# shema.net
KiCad netlist of a schematic drawn in EAGLE
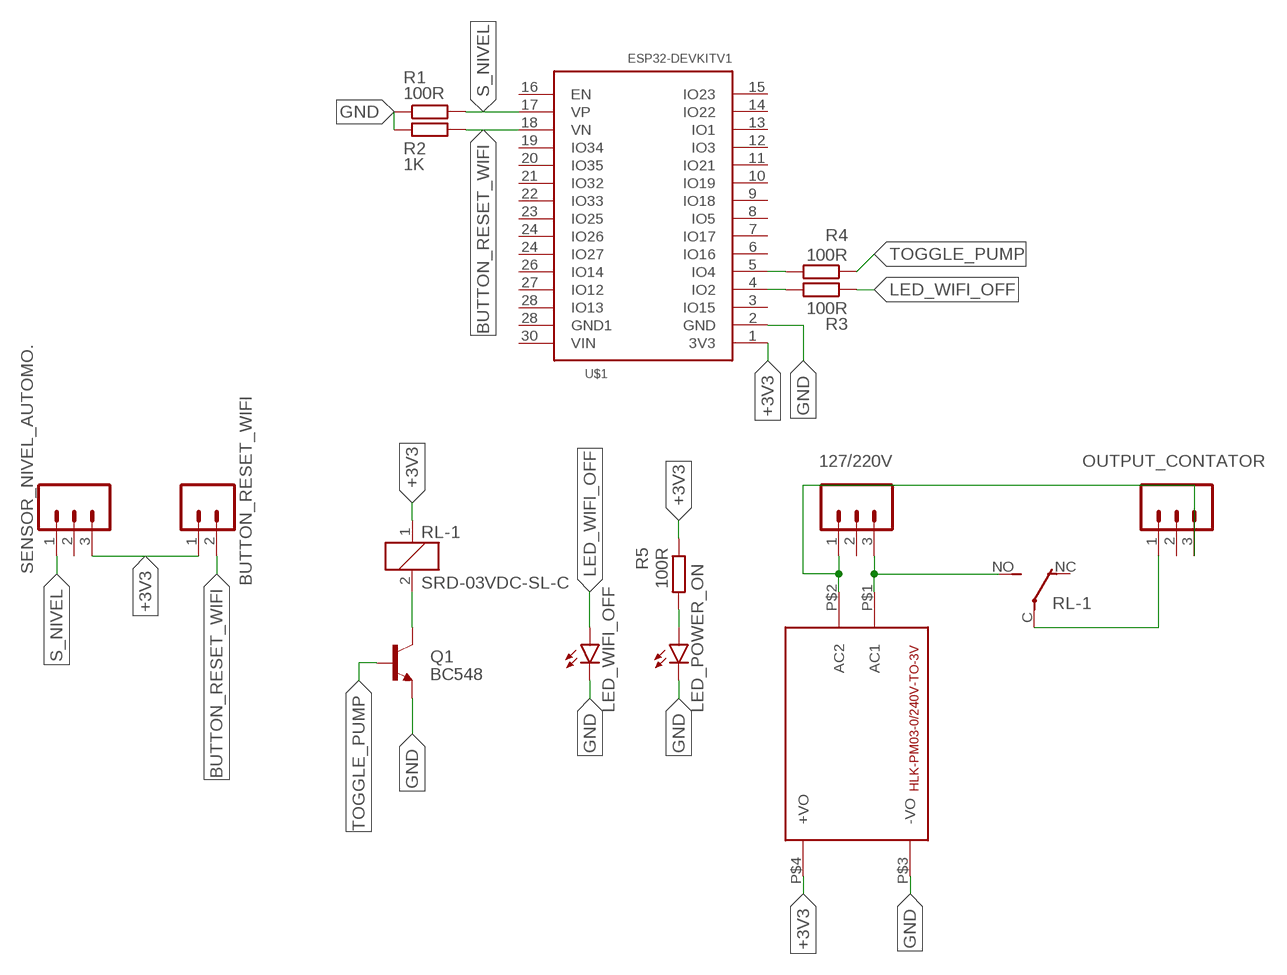
[diagram p0: schematic, sheet 1]

(export (version "E")
  (design (tool "Eeschema 10.0.6"))
  (components
    (comp (ref "127/220V")
      (value "M03")
      (footprint "eagle-import:03P")
      (libsource (lib "eagle-import") (part "M03"))
    )
    (comp (ref "BUTTON_RESET_WIFI")
      (value "M02")
      (footprint "eagle-import:02P")
      (libsource (lib "eagle-import") (part "M02"))
    )
    (comp (ref "HLK-PM03-0/240V-TO-3V")
      (value "HLK-PM013W")
      (footprint "eagle-import:HLK-PM01")
      (libsource (lib "eagle-import") (part "HLK-PM013W"))
    )
    (comp (ref "LED_POWER_ON")
      (value "LED3MM")
      (footprint "eagle-import:LED3MM")
      (libsource (lib "eagle-import") (part "LED3MM"))
    )
    (comp (ref "LED_WIFI_OFF")
      (value "LED3MM")
      (footprint "eagle-import:LED3MM")
      (libsource (lib "eagle-import") (part "LED3MM"))
    )
    (comp (ref "OUTPUT_CONTATOR")
      (value "M03")
      (footprint "eagle-import:03P")
      (libsource (lib "eagle-import") (part "M03"))
    )
    (comp (ref "Q1")
      (value "BC548")
      (footprint "eagle-import:TO92-EBC")
      (libsource (lib "eagle-import") (part "BC548"))
    )
    (comp (ref "R1")
      (value "100R")
      (footprint "eagle-import:0207_10")
      (libsource (lib "eagle-import") (part "R-EU_0207/10"))
    )
    (comp (ref "R2")
      (value "1K")
      (footprint "eagle-import:0207_10")
      (libsource (lib "eagle-import") (part "R-EU_0207/10"))
    )
    (comp (ref "R3")
      (value "100R")
      (footprint "eagle-import:0207_10")
      (libsource (lib "eagle-import") (part "R-EU_0207/10"))
    )
    (comp (ref "R4")
      (value "100R")
      (footprint "eagle-import:0207_10")
      (libsource (lib "eagle-import") (part "R-EU_0207/10"))
    )
    (comp (ref "R5")
      (value "100R")
      (footprint "eagle-import:0207_10")
      (libsource (lib "eagle-import") (part "R-EU_0207/10"))
    )
    (comp (ref "RL-1")
      (value "SRD-03VDC-SL-C")
      (footprint "eagle-import:CQ1")
      (libsource (lib "eagle-import") (part "CQ1-12V"))
    )
    (comp (ref "SENSOR_NIVEL_AUTOMO.")
      (value "M03")
      (footprint "eagle-import:03P")
      (libsource (lib "eagle-import") (part "M03"))
    )
    (comp (ref "U$1")
      (value "ESP32DEVKITV1")
      (footprint "eagle-import:ESP32-DEVKITV1")
      (libsource (lib "eagle-import") (part "ESP32DEVKITV1"))
    )
  )
  (nets
    (net (code "1") (name "+3V3") (class "Default")
      (node (ref "BUTTON_RESET_WIFI") (pin "1") (pinfunction "1_1") (pintype "passive"))
      (node (ref "HLK-PM03-0/240V-TO-3V") (pin "P$4") (pinfunction "+VO_P$4") (pintype "bidirectional"))
      (node (ref "R5") (pin "1") (pinfunction "1_1") (pintype "passive"))
      (node (ref "RL-1") (pin "1") (pinfunction "1_1") (pintype "passive"))
      (node (ref "SENSOR_NIVEL_AUTOMO.") (pin "3") (pinfunction "3_3") (pintype "passive"))
      (node (ref "U$1") (pin "1") (pinfunction "3V3_1") (pintype "bidirectional"))
    )
    (net (code "2") (name "BUTTON_RESET_WIFI") (class "Default")
      (node (ref "BUTTON_RESET_WIFI") (pin "2") (pinfunction "2_2") (pintype "passive"))
      (node (ref "R2") (pin "2") (pinfunction "2_2") (pintype "passive"))
      (node (ref "U$1") (pin "18") (pinfunction "VN_18") (pintype "bidirectional"))
    )
    (net (code "3") (name "GND") (class "Default")
      (node (ref "HLK-PM03-0/240V-TO-3V") (pin "P$3") (pinfunction "-VO_P$3") (pintype "bidirectional"))
      (node (ref "LED_POWER_ON") (pin "K") (pinfunction "C_K") (pintype "passive"))
      (node (ref "LED_WIFI_OFF") (pin "K") (pinfunction "C_K") (pintype "passive"))
      (node (ref "Q1") (pin "E") (pinfunction "E_E") (pintype "passive"))
      (node (ref "R1") (pin "1") (pinfunction "1_1") (pintype "passive"))
      (node (ref "R2") (pin "1") (pinfunction "1_1") (pintype "passive"))
      (node (ref "U$1") (pin "2") (pinfunction "GND_2") (pintype "bidirectional"))
    )
    (net (code "4") (name "LED_WIFI_OFF") (class "Default")
      (node (ref "LED_WIFI_OFF") (pin "A") (pinfunction "A_A") (pintype "passive"))
      (node (ref "R3") (pin "1") (pinfunction "1_1") (pintype "passive"))
    )
    (net (code "5") (name "Net-(HLK-PM03-0/240V-TO-3V-AC1)") (class "Default")
      (node (ref "127/220V") (pin "3") (pinfunction "3_3") (pintype "passive"))
      (node (ref "HLK-PM03-0/240V-TO-3V") (pin "P$1") (pinfunction "AC1_P$1") (pintype "bidirectional"))
      (node (ref "RL-1") (pin "NO") (pinfunction "S_NO") (pintype "passive"))
    )
    (net (code "6") (name "Net-(HLK-PM03-0/240V-TO-3V-AC2)") (class "Default")
      (node (ref "127/220V") (pin "1") (pinfunction "1_1") (pintype "passive"))
      (node (ref "HLK-PM03-0/240V-TO-3V") (pin "P$2") (pinfunction "AC2_P$2") (pintype "bidirectional"))
      (node (ref "OUTPUT_CONTATOR") (pin "3") (pinfunction "3_3") (pintype "passive"))
    )
    (net (code "7") (name "Net-(LED_POWER_ON-PadA)") (class "Default")
      (node (ref "LED_POWER_ON") (pin "A") (pinfunction "A_A") (pintype "passive"))
      (node (ref "R5") (pin "2") (pinfunction "2_2") (pintype "passive"))
    )
    (net (code "8") (name "Net-(Q1-PadC)") (class "Default")
      (node (ref "Q1") (pin "C") (pinfunction "C_C") (pintype "passive"))
      (node (ref "RL-1") (pin "2") (pinfunction "2_2") (pintype "passive"))
    )
    (net (code "9") (name "Net-(RL-1B-P)") (class "Default")
      (node (ref "OUTPUT_CONTATOR") (pin "1") (pinfunction "1_1") (pintype "passive"))
      (node (ref "RL-1") (pin "C") (pinfunction "P_C") (pintype "passive"))
    )
    (net (code "10") (name "Net-(U$1-IO2)") (class "Default")
      (node (ref "R3") (pin "2") (pinfunction "2_2") (pintype "passive"))
      (node (ref "U$1") (pin "4") (pinfunction "IO2_4") (pintype "bidirectional"))
    )
    (net (code "11") (name "Net-(U$1-IO4)") (class "Default")
      (node (ref "R4") (pin "2") (pinfunction "2_2") (pintype "passive"))
      (node (ref "U$1") (pin "5") (pinfunction "IO4_5") (pintype "bidirectional"))
    )
    (net (code "12") (name "S_NIVEL") (class "Default")
      (node (ref "R1") (pin "2") (pinfunction "2_2") (pintype "passive"))
      (node (ref "SENSOR_NIVEL_AUTOMO.") (pin "1") (pinfunction "1_1") (pintype "passive"))
      (node (ref "U$1") (pin "17") (pinfunction "VP_17") (pintype "bidirectional"))
    )
    (net (code "13") (name "TOGGLE_PUMP") (class "Default")
      (node (ref "Q1") (pin "B") (pinfunction "B_B") (pintype "passive"))
      (node (ref "R4") (pin "1") (pinfunction "1_1") (pintype "passive"))
    )
    (net (code "14") (name "unconnected-(127/220V-Pad2)") (class "Default")
      (node (ref "127/220V") (pin "2") (pinfunction "2_2") (pintype "passive"))
    )
    (net (code "15") (name "unconnected-(OUTPUT_CONTATOR-Pad2)") (class "Default")
      (node (ref "OUTPUT_CONTATOR") (pin "2") (pinfunction "2_2") (pintype "passive"))
    )
    (net (code "16") (name "unconnected-(RL-1B-O-PadNC)") (class "Default")
      (node (ref "RL-1") (pin "NC") (pinfunction "O_NC") (pintype "passive"))
    )
    (net (code "17") (name "unconnected-(SENSOR_NIVEL_AUTOMO.-Pad2)") (class "Default")
      (node (ref "SENSOR_NIVEL_AUTOMO.") (pin "2") (pinfunction "2_2") (pintype "passive"))
    )
    (net (code "18") (name "unconnected-(U$1-EN-Pad16)") (class "Default")
      (node (ref "U$1") (pin "16") (pinfunction "EN_16") (pintype "bidirectional"))
    )
    (net (code "19") (name "unconnected-(U$1-GND1-Pad28)") (class "Default")
      (node (ref "U$1") (pin "28") (pinfunction "GND1_28") (pintype "bidirectional"))
    )
    (net (code "20") (name "unconnected-(U$1-IO1-Pad13)") (class "Default")
      (node (ref "U$1") (pin "13") (pinfunction "IO1_13") (pintype "bidirectional"))
    )
    (net (code "21") (name "unconnected-(U$1-IO3-Pad12)") (class "Default")
      (node (ref "U$1") (pin "12") (pinfunction "IO3_12") (pintype "bidirectional"))
    )
    (net (code "22") (name "unconnected-(U$1-IO5-Pad8)") (class "Default")
      (node (ref "U$1") (pin "8") (pinfunction "IO5_8") (pintype "bidirectional"))
    )
    (net (code "23") (name "unconnected-(U$1-IO12-Pad27)") (class "Default")
      (node (ref "U$1") (pin "27") (pinfunction "IO12_27") (pintype "bidirectional"))
    )
    (net (code "24") (name "unconnected-(U$1-IO13-Pad28)") (class "Default")
      (node (ref "U$1") (pin "28") (pinfunction "IO13_28") (pintype "bidirectional"))
    )
    (net (code "25") (name "unconnected-(U$1-IO14-Pad26)") (class "Default")
      (node (ref "U$1") (pin "26") (pinfunction "IO14_26") (pintype "bidirectional"))
    )
    (net (code "26") (name "unconnected-(U$1-IO15-Pad3)") (class "Default")
      (node (ref "U$1") (pin "3") (pinfunction "IO15_3") (pintype "bidirectional"))
    )
    (net (code "27") (name "unconnected-(U$1-IO16-Pad6)") (class "Default")
      (node (ref "U$1") (pin "6") (pinfunction "IO16_6") (pintype "bidirectional"))
    )
    (net (code "28") (name "unconnected-(U$1-IO17-Pad7)") (class "Default")
      (node (ref "U$1") (pin "7") (pinfunction "IO17_7") (pintype "bidirectional"))
    )
    (net (code "29") (name "unconnected-(U$1-IO18-Pad9)") (class "Default")
      (node (ref "U$1") (pin "9") (pinfunction "IO18_9") (pintype "bidirectional"))
    )
    (net (code "30") (name "unconnected-(U$1-IO19-Pad10)") (class "Default")
      (node (ref "U$1") (pin "10") (pinfunction "IO19_10") (pintype "bidirectional"))
    )
    (net (code "31") (name "unconnected-(U$1-IO21-Pad11)") (class "Default")
      (node (ref "U$1") (pin "11") (pinfunction "IO21_11") (pintype "bidirectional"))
    )
    (net (code "32") (name "unconnected-(U$1-IO22-Pad14)") (class "Default")
      (node (ref "U$1") (pin "14") (pinfunction "IO22_14") (pintype "bidirectional"))
    )
    (net (code "33") (name "unconnected-(U$1-IO23-Pad15)") (class "Default")
      (node (ref "U$1") (pin "15") (pinfunction "IO23_15") (pintype "bidirectional"))
    )
    (net (code "34") (name "unconnected-(U$1-IO25-Pad23)") (class "Default")
      (node (ref "U$1") (pin "23") (pinfunction "IO25_23") (pintype "bidirectional"))
    )
    (net (code "35") (name "unconnected-(U$1-IO26-Pad24)") (class "Default")
      (node (ref "U$1") (pin "24") (pinfunction "IO26_24") (pintype "bidirectional"))
    )
    (net (code "36") (name "unconnected-(U$1-IO27-Pad24)") (class "Default")
      (node (ref "U$1") (pin "24") (pinfunction "IO27_24") (pintype "bidirectional"))
    )
    (net (code "37") (name "unconnected-(U$1-IO32-Pad21)") (class "Default")
      (node (ref "U$1") (pin "21") (pinfunction "IO32_21") (pintype "bidirectional"))
    )
    (net (code "38") (name "unconnected-(U$1-IO33-Pad22)") (class "Default")
      (node (ref "U$1") (pin "22") (pinfunction "IO33_22") (pintype "bidirectional"))
    )
    (net (code "39") (name "unconnected-(U$1-IO34-Pad19)") (class "Default")
      (node (ref "U$1") (pin "19") (pinfunction "IO34_19") (pintype "bidirectional"))
    )
    (net (code "40") (name "unconnected-(U$1-IO35-Pad20)") (class "Default")
      (node (ref "U$1") (pin "20") (pinfunction "IO35_20") (pintype "bidirectional"))
    )
    (net (code "41") (name "unconnected-(U$1-VIN-Pad30)") (class "Default")
      (node (ref "U$1") (pin "30") (pinfunction "VIN_30") (pintype "bidirectional"))
    )
  )
)
